# USB_port.net
KiCad netlist of a schematic drawn in Altium Designer
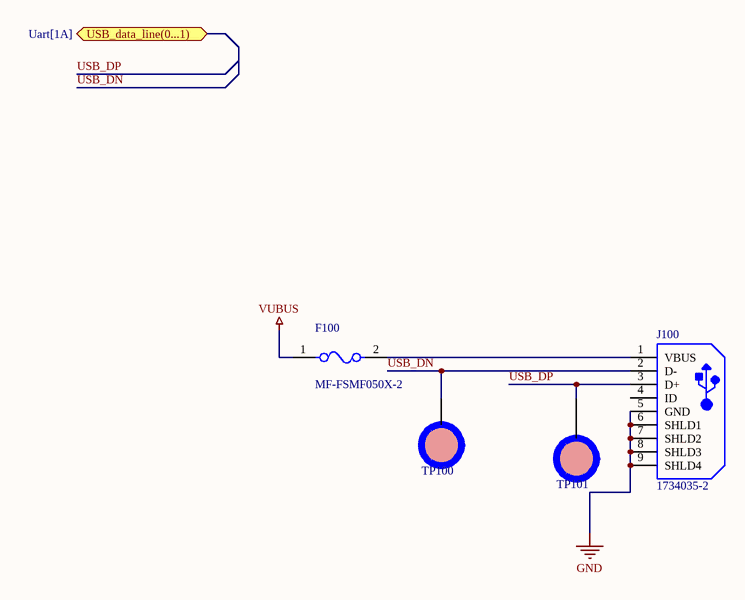
[diagram p0: USB_port.SchDoc]

(export (version "E")
  (design (tool "Eeschema 10.0.6"))
  (components
    (comp (ref "F100")
      (value "MF-FSMF050X-2")
      (footprint "FP-MF-FSMF-MFG")
      (description "PTC RESET FUSE 6V 500MA 0603")
      (fields
        (field (name "MANUFACTURER") "Bourns Inc.")
        (field (name "OCTOPART") "https://octopart.com/mf-fsmf050x-2-bourns-10470804")
      )
      (libsource (lib "Altium Content Vault") (part "5bcf9b9f640e542cf0359d10258e979"))
    )
    (comp (ref "J100")
      (value "1734035-2")
      (footprint "TECO-1734035-2-5_V")
      (description "Surface Mount Type B Mini USB, 5 Positions, 0.8 mm Pitch, 0 to 50 degC, RoHS, Tape and Reel")
      (fields (field (name "MANUFACTURER") "TE Connectivity"))
      (libsource (lib "Altium Content Vault") (part "USB-5-4SHLD"))
    )
    (comp (ref "TP100") (value "TP") (footprint "TEST_POINT") (libsource (lib "Schlib1") (part "TEST_POINT")))
    (comp (ref "TP101") (value "TP") (footprint "TEST_POINT") (libsource (lib "Schlib1") (part "TEST_POINT")))
  )
  (nets
    (net (code "1") (name "/USB_DN") (class "Default")
      (node (ref "J100") (pin "2") (pinfunction "D-_2") (pintype "passive"))
    )
    (net (code "2") (name "/USB_DP") (class "Default")
      (node (ref "J100") (pin "3") (pinfunction "D+_3") (pintype "passive"))
    )
    (net (code "4") (name "GND") (class "Default")
      (node (ref "J100") (pin "5") (pinfunction "GND_5") (pintype "power_in"))
      (node (ref "J100") (pin "6") (pinfunction "SHLD1_6") (pintype "passive"))
      (node (ref "J100") (pin "7") (pinfunction "SHLD2_7") (pintype "passive"))
      (node (ref "J100") (pin "8") (pinfunction "SHLD3_8") (pintype "passive"))
      (node (ref "J100") (pin "9") (pinfunction "SHLD4_9") (pintype "passive"))
    )
    (net (code "5") (name "Net-(J100-VBUS)") (class "Default")
      (node (ref "F100") (pin "2") (pinfunction "2_2") (pintype "passive"))
      (node (ref "J100") (pin "1") (pinfunction "VBUS_1") (pintype "power_in"))
    )
    (net (code "6") (name "VUBUS") (class "Default")
      (node (ref "F100") (pin "1") (pinfunction "1_1") (pintype "passive"))
    )
    (net (code "7") (name "unconnected-(J100-ID-Pad4)") (class "Default")
      (node (ref "J100") (pin "4") (pinfunction "ID_4") (pintype "passive"))
    )
    (net (code "8") (name "unconnected-(TP100-Pad1)") (class "Default")
      (node (ref "TP100") (pin "1") (pinfunction "1_1") (pintype "passive"))
    )
    (net (code "9") (name "unconnected-(TP101-Pad1)") (class "Default")
      (node (ref "TP101") (pin "1") (pinfunction "1_1") (pintype "passive"))
    )
  )
)
